# Base_Board.net
KiCad netlist of a schematic drawn in EAGLE
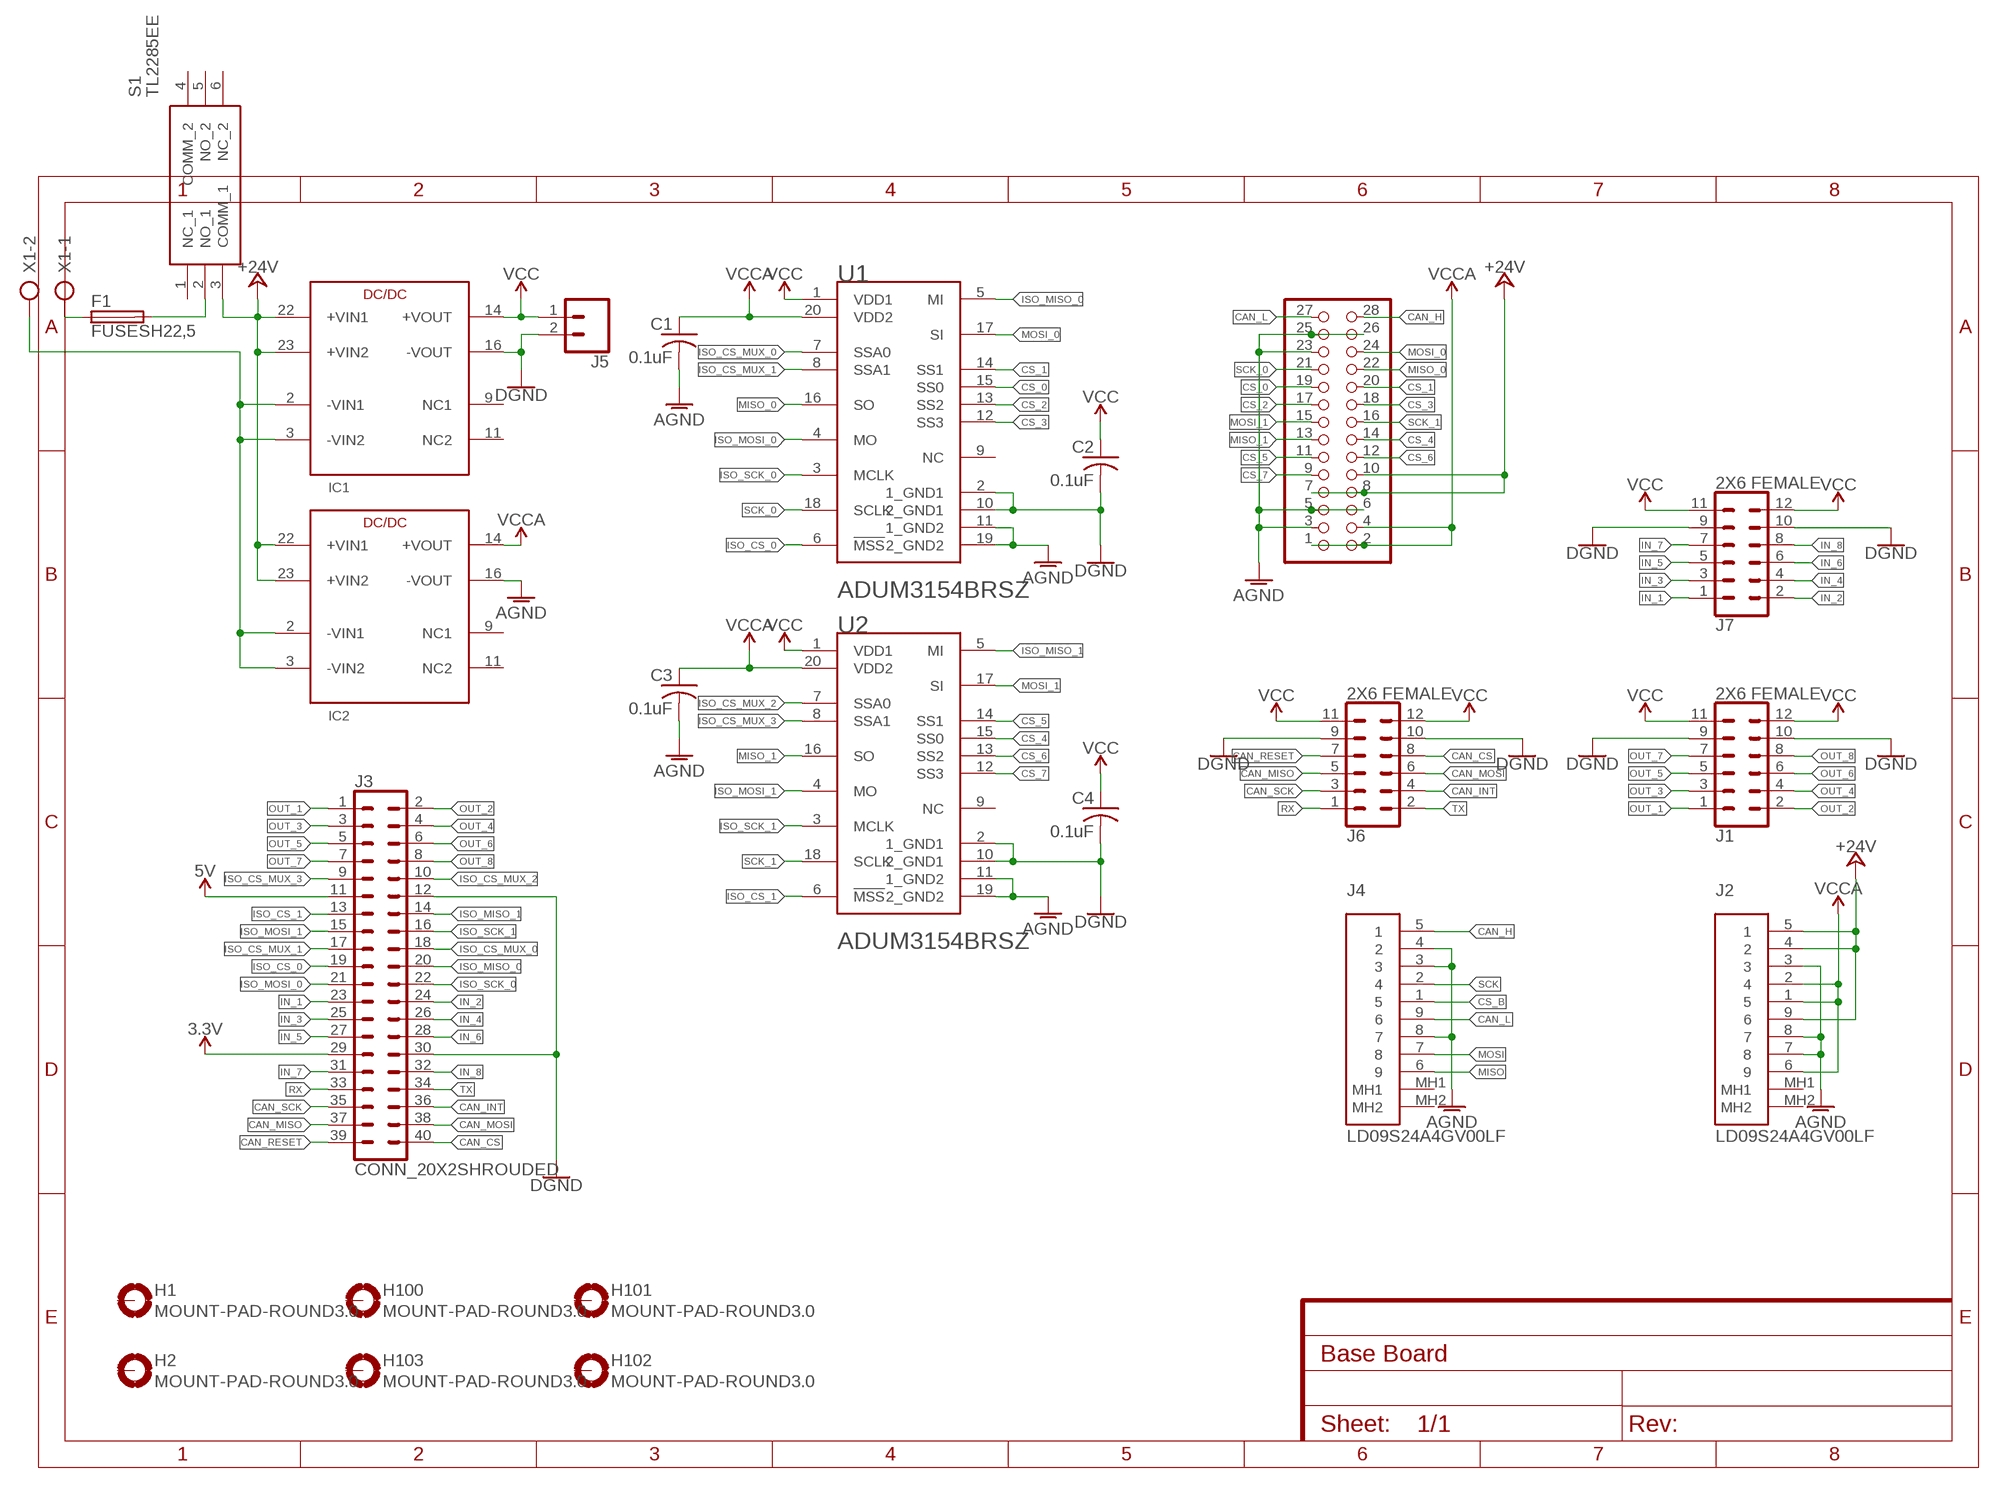
[diagram p0: schematic, sheet 1]

(export (version "E")
  (design (tool "Eeschema 10.0.6"))
  (components
    (comp (ref "C1")
      (value "0.1uF")
      (footprint "eagle-import:C0805")
      (libsource (lib "eagle-import") (part "C-USC0805"))
    )
    (comp (ref "C2")
      (value "0.1uF")
      (footprint "eagle-import:C0805")
      (libsource (lib "eagle-import") (part "C-USC0805"))
    )
    (comp (ref "C3")
      (value "0.1uF")
      (footprint "eagle-import:C0805")
      (libsource (lib "eagle-import") (part "C-USC0805"))
    )
    (comp (ref "C4")
      (value "0.1uF")
      (footprint "eagle-import:C0805")
      (libsource (lib "eagle-import") (part "C-USC0805"))
    )
    (comp (ref "F1")
      (value "FUSESH22,5")
      (footprint "eagle-import:SH22,5")
      (libsource (lib "eagle-import") (part "FUSESH22,5"))
    )
    (comp (ref "H1")
      (value "MOUNT-PAD-ROUND3.0")
      (footprint "eagle-import:3,0-PAD")
      (libsource (lib "eagle-import") (part "MOUNT-PAD-ROUND3.0"))
    )
    (comp (ref "H2")
      (value "MOUNT-PAD-ROUND3.0")
      (footprint "eagle-import:3,0-PAD")
      (libsource (lib "eagle-import") (part "MOUNT-PAD-ROUND3.0"))
    )
    (comp (ref "H100")
      (value "MOUNT-PAD-ROUND3.0")
      (footprint "eagle-import:3,0-PAD")
      (libsource (lib "eagle-import") (part "MOUNT-PAD-ROUND3.0"))
    )
    (comp (ref "H101")
      (value "MOUNT-PAD-ROUND3.0")
      (footprint "eagle-import:3,0-PAD")
      (libsource (lib "eagle-import") (part "MOUNT-PAD-ROUND3.0"))
    )
    (comp (ref "H102")
      (value "MOUNT-PAD-ROUND3.0")
      (footprint "eagle-import:3,0-PAD")
      (libsource (lib "eagle-import") (part "MOUNT-PAD-ROUND3.0"))
    )
    (comp (ref "H103")
      (value "MOUNT-PAD-ROUND3.0")
      (footprint "eagle-import:3,0-PAD")
      (libsource (lib "eagle-import") (part "MOUNT-PAD-ROUND3.0"))
    )
    (comp (ref "IC1")
      (value "TEL_5_SERIES")
      (footprint "eagle-import:TEL_5_SERIES")
      (libsource (lib "eagle-import") (part "TEL_5_SERIES"))
    )
    (comp (ref "IC2")
      (value "TEL_5_SERIES")
      (footprint "eagle-import:TEL_5_SERIES")
      (libsource (lib "eagle-import") (part "TEL_5_SERIES"))
    )
    (comp (ref "J1")
      (value "2X6 FEMALE")
      (footprint "eagle-import:2X6")
      (libsource (lib "eagle-import") (part "CONN_06X2PTH_FEMALE"))
    )
    (comp (ref "J2")
      (value "LD09S24A4GV00LF")
      (footprint "eagle-import:LD09S24A4GV00LF")
      (fields
        (field (name "DIGIKEY_PART_NUMBER") "609-5190-ND")
        (field (name "MANUFACTURER") "Amphenol ICC (FCI)")
        (field (name "CREATED_BY") "PCBLayout.com")
      )
      (libsource (lib "eagle-import") (part "LD09S24A4GV00LF"))
    )
    (comp (ref "J3")
      (value "CONN_20X2SHROUDED")
      (footprint "eagle-import:2X20_SHROUDED")
      (libsource (lib "eagle-import") (part "CONN_20X2SHROUDED"))
    )
    (comp (ref "J4")
      (value "LD09S24A4GV00LF")
      (footprint "eagle-import:LD09S24A4GV00LF")
      (fields
        (field (name "DIGIKEY_PART_NUMBER") "609-5190-ND")
        (field (name "MANUFACTURER") "Amphenol ICC (FCI)")
        (field (name "CREATED_BY") "PCBLayout.com")
      )
      (libsource (lib "eagle-import") (part "LD09S24A4GV00LF"))
    )
    (comp (ref "J5")
      (value "CONN_02POLAR_LOCK")
      (footprint "eagle-import:MOLEX-1X2_LOCK")
      (libsource (lib "eagle-import") (part "CONN_02POLAR_LOCK"))
    )
    (comp (ref "J6")
      (value "2X6 FEMALE")
      (footprint "eagle-import:2X6")
      (libsource (lib "eagle-import") (part "CONN_06X2PTH_FEMALE"))
    )
    (comp (ref "J7")
      (value "2X6 FEMALE")
      (footprint "eagle-import:2X6")
      (libsource (lib "eagle-import") (part "CONN_06X2PTH_FEMALE"))
    )
    (comp (ref "JP1")
      (value "PINHD-2X14/90")
      (footprint "eagle-import:2X14_90")
      (libsource (lib "eagle-import") (part "PINHD-2X14/90"))
    )
    (comp (ref "S1")
      (value "TL2285EE")
      (footprint "eagle-import:TL2285EE")
      (fields (field (name "MOUSER_PART_NUMBER") "612-TL2285EE"))
      (libsource (lib "eagle-import") (part "TL2285EE"))
    )
    (comp (ref "U1")
      (value "ANALOG_DEVICES_INC_ADUM3154BRSZANALOG_DEVICES_INC_ADUM3154BRSZ_0_0")
      (footprint "eagle-import:ANALOG_DEVICES_INC_ADUM3154BRSZ_0")
      (fields
        (field (name "DIGIKEY_PART_NUMBER") "ADUM3154BRSZ-ND")
        (field (name "MF") "Analog Devices Inc")
        (field (name "MOUSER_PART_NUMBER") "584-ADUM3154BRSZ")
      )
      (libsource (lib "eagle-import") (part "ANALOG_DEVICES_INC_ADUM3154BRSZANALOG_DEVICES_INC_ADUM3154BRSZ_0_0"))
    )
    (comp (ref "U2")
      (value "ANALOG_DEVICES_INC_ADUM3154BRSZANALOG_DEVICES_INC_ADUM3154BRSZ_0_0")
      (footprint "eagle-import:ANALOG_DEVICES_INC_ADUM3154BRSZ_0")
      (fields
        (field (name "DIGIKEY_PART_NUMBER") "ADUM3154BRSZ-ND")
        (field (name "MF") "Analog Devices Inc")
        (field (name "MOUSER_PART_NUMBER") "584-ADUM3154BRSZ")
      )
      (libsource (lib "eagle-import") (part "ANALOG_DEVICES_INC_ADUM3154BRSZANALOG_DEVICES_INC_ADUM3154BRSZ_0_0"))
    )
    (comp (ref "X1")
      (value "AK500/2-H")
      (footprint "eagle-import:AK500_2-H")
      (libsource (lib "eagle-import") (part "AK500/2-H"))
    )
  )
  (nets
    (net (code "1") (name "+24V") (class "Default")
      (node (ref "IC1") (pin "22") (pinfunction "+VIN1_22") (pintype "input"))
      (node (ref "IC1") (pin "23") (pinfunction "+VIN2_23") (pintype "input"))
      (node (ref "IC2") (pin "22") (pinfunction "+VIN1_22") (pintype "input"))
      (node (ref "IC2") (pin "23") (pinfunction "+VIN2_23") (pintype "input"))
      (node (ref "J2") (pin "4") (pinfunction "2_4") (pintype "passive"))
      (node (ref "J2") (pin "5") (pinfunction "1_5") (pintype "passive"))
      (node (ref "J2") (pin "9") (pinfunction "6_9") (pintype "passive"))
      (node (ref "JP1") (pin "10") (pinfunction "10_10") (pintype "passive"))
      (node (ref "JP1") (pin "7") (pinfunction "7_7") (pintype "passive"))
      (node (ref "JP1") (pin "8") (pinfunction "8_8") (pintype "passive"))
      (node (ref "S1") (pin "3") (pinfunction "COMM_1_3") (pintype "bidirectional"))
    )
    (net (code "2") (name "3.3V") (class "Default")
      (node (ref "J3") (pin "29") (pinfunction "29_29") (pintype "passive"))
    )
    (net (code "3") (name "5V") (class "Default")
      (node (ref "J3") (pin "11") (pinfunction "11_11") (pintype "passive"))
    )
    (net (code "4") (name "AGND") (class "Default")
      (node (ref "C1") (pin "2") (pinfunction "2_2") (pintype "passive"))
      (node (ref "C3") (pin "2") (pinfunction "2_2") (pintype "passive"))
      (node (ref "IC2") (pin "16") (pinfunction "-VOUT_16") (pintype "passive"))
      (node (ref "J2") (pin "3") (pinfunction "3_3") (pintype "passive"))
      (node (ref "J2") (pin "7") (pinfunction "8_7") (pintype "passive"))
      (node (ref "J2") (pin "8") (pinfunction "7_8") (pintype "passive"))
      (node (ref "J4") (pin "3") (pinfunction "3_3") (pintype "passive"))
      (node (ref "J4") (pin "4") (pinfunction "2_4") (pintype "passive"))
      (node (ref "J4") (pin "8") (pinfunction "7_8") (pintype "passive"))
      (node (ref "JP1") (pin "23") (pinfunction "23_23") (pintype "passive"))
      (node (ref "JP1") (pin "25") (pinfunction "25_25") (pintype "passive"))
      (node (ref "JP1") (pin "26") (pinfunction "26_26") (pintype "passive"))
      (node (ref "JP1") (pin "3") (pinfunction "3_3") (pintype "passive"))
      (node (ref "JP1") (pin "5") (pinfunction "5_5") (pintype "passive"))
      (node (ref "JP1") (pin "6") (pinfunction "6_6") (pintype "passive"))
      (node (ref "U1") (pin "11") (pinfunction "1_GND2_11") (pintype "power_in"))
      (node (ref "U1") (pin "19") (pinfunction "2_GND2_19") (pintype "power_in"))
      (node (ref "U2") (pin "11") (pinfunction "1_GND2_11") (pintype "power_in"))
      (node (ref "U2") (pin "19") (pinfunction "2_GND2_19") (pintype "power_in"))
    )
    (net (code "5") (name "CAN_CS") (class "Default")
      (node (ref "J3") (pin "40") (pinfunction "40_40") (pintype "passive"))
      (node (ref "J6") (pin "8") (pinfunction "8_8") (pintype "passive"))
    )
    (net (code "6") (name "CAN_H") (class "Default")
      (node (ref "J4") (pin "5") (pinfunction "1_5") (pintype "passive"))
      (node (ref "JP1") (pin "28") (pinfunction "28_28") (pintype "passive"))
    )
    (net (code "7") (name "CAN_INT") (class "Default")
      (node (ref "J3") (pin "36") (pinfunction "36_36") (pintype "passive"))
      (node (ref "J6") (pin "4") (pinfunction "4_4") (pintype "passive"))
    )
    (net (code "8") (name "CAN_L") (class "Default")
      (node (ref "J4") (pin "9") (pinfunction "6_9") (pintype "passive"))
      (node (ref "JP1") (pin "27") (pinfunction "27_27") (pintype "passive"))
    )
    (net (code "9") (name "CAN_MISO") (class "Default")
      (node (ref "J3") (pin "37") (pinfunction "37_37") (pintype "passive"))
      (node (ref "J6") (pin "5") (pinfunction "5_5") (pintype "passive"))
    )
    (net (code "10") (name "CAN_MOSI") (class "Default")
      (node (ref "J3") (pin "38") (pinfunction "38_38") (pintype "passive"))
      (node (ref "J6") (pin "6") (pinfunction "6_6") (pintype "passive"))
    )
    (net (code "11") (name "CAN_RESET") (class "Default")
      (node (ref "J3") (pin "39") (pinfunction "39_39") (pintype "passive"))
      (node (ref "J6") (pin "7") (pinfunction "7_7") (pintype "passive"))
    )
    (net (code "12") (name "CAN_SCK") (class "Default")
      (node (ref "J3") (pin "35") (pinfunction "35_35") (pintype "passive"))
      (node (ref "J6") (pin "3") (pinfunction "3_3") (pintype "passive"))
    )
    (net (code "13") (name "CS_0") (class "Default")
      (node (ref "JP1") (pin "19") (pinfunction "19_19") (pintype "passive"))
      (node (ref "U1") (pin "15") (pinfunction "SS0_15") (pintype "output"))
    )
    (net (code "14") (name "CS_1") (class "Default")
      (node (ref "JP1") (pin "20") (pinfunction "20_20") (pintype "passive"))
      (node (ref "U1") (pin "14") (pinfunction "SS1_14") (pintype "output"))
    )
    (net (code "15") (name "CS_2") (class "Default")
      (node (ref "JP1") (pin "17") (pinfunction "17_17") (pintype "passive"))
      (node (ref "U1") (pin "13") (pinfunction "SS2_13") (pintype "output"))
    )
    (net (code "16") (name "CS_3") (class "Default")
      (node (ref "JP1") (pin "18") (pinfunction "18_18") (pintype "passive"))
      (node (ref "U1") (pin "12") (pinfunction "SS3_12") (pintype "output"))
    )
    (net (code "17") (name "CS_4") (class "Default")
      (node (ref "JP1") (pin "14") (pinfunction "14_14") (pintype "passive"))
      (node (ref "U2") (pin "15") (pinfunction "SS0_15") (pintype "output"))
    )
    (net (code "18") (name "CS_5") (class "Default")
      (node (ref "JP1") (pin "11") (pinfunction "11_11") (pintype "passive"))
      (node (ref "U2") (pin "14") (pinfunction "SS1_14") (pintype "output"))
    )
    (net (code "19") (name "CS_6") (class "Default")
      (node (ref "JP1") (pin "12") (pinfunction "12_12") (pintype "passive"))
      (node (ref "U2") (pin "13") (pinfunction "SS2_13") (pintype "output"))
    )
    (net (code "20") (name "CS_7") (class "Default")
      (node (ref "JP1") (pin "9") (pinfunction "9_9") (pintype "passive"))
      (node (ref "U2") (pin "12") (pinfunction "SS3_12") (pintype "output"))
    )
    (net (code "21") (name "CS_B") (class "Default")
      (node (ref "J4") (pin "1") (pinfunction "5_1") (pintype "passive"))
    )
    (net (code "22") (name "DGND") (class "Default")
      (node (ref "C2") (pin "2") (pinfunction "2_2") (pintype "passive"))
      (node (ref "C4") (pin "2") (pinfunction "2_2") (pintype "passive"))
      (node (ref "IC1") (pin "16") (pinfunction "-VOUT_16") (pintype "passive"))
      (node (ref "J1") (pin "10") (pinfunction "10_10") (pintype "passive"))
      (node (ref "J1") (pin "9") (pinfunction "9_9") (pintype "passive"))
      (node (ref "J3") (pin "12") (pinfunction "12_12") (pintype "passive"))
      (node (ref "J3") (pin "30") (pinfunction "30_30") (pintype "passive"))
      (node (ref "J5") (pin "2") (pinfunction "2_2") (pintype "passive"))
      (node (ref "J6") (pin "10") (pinfunction "10_10") (pintype "passive"))
      (node (ref "J6") (pin "9") (pinfunction "9_9") (pintype "passive"))
      (node (ref "J7") (pin "10") (pinfunction "10_10") (pintype "passive"))
      (node (ref "J7") (pin "9") (pinfunction "9_9") (pintype "passive"))
      (node (ref "U1") (pin "10") (pinfunction "2_GND1_10") (pintype "power_in"))
      (node (ref "U1") (pin "2") (pinfunction "1_GND1_2") (pintype "power_in"))
      (node (ref "U2") (pin "10") (pinfunction "2_GND1_10") (pintype "power_in"))
      (node (ref "U2") (pin "2") (pinfunction "1_GND1_2") (pintype "power_in"))
    )
    (net (code "23") (name "IN_1") (class "Default")
      (node (ref "J3") (pin "23") (pinfunction "23_23") (pintype "passive"))
      (node (ref "J7") (pin "1") (pinfunction "1_1") (pintype "passive"))
    )
    (net (code "24") (name "IN_2") (class "Default")
      (node (ref "J3") (pin "24") (pinfunction "24_24") (pintype "passive"))
      (node (ref "J7") (pin "2") (pinfunction "2_2") (pintype "passive"))
    )
    (net (code "25") (name "IN_3") (class "Default")
      (node (ref "J3") (pin "25") (pinfunction "25_25") (pintype "passive"))
      (node (ref "J7") (pin "3") (pinfunction "3_3") (pintype "passive"))
    )
    (net (code "26") (name "IN_4") (class "Default")
      (node (ref "J3") (pin "26") (pinfunction "26_26") (pintype "passive"))
      (node (ref "J7") (pin "4") (pinfunction "4_4") (pintype "passive"))
    )
    (net (code "27") (name "IN_5") (class "Default")
      (node (ref "J3") (pin "27") (pinfunction "27_27") (pintype "passive"))
      (node (ref "J7") (pin "5") (pinfunction "5_5") (pintype "passive"))
    )
    (net (code "28") (name "IN_6") (class "Default")
      (node (ref "J3") (pin "28") (pinfunction "28_28") (pintype "passive"))
      (node (ref "J7") (pin "6") (pinfunction "6_6") (pintype "passive"))
    )
    (net (code "29") (name "IN_7") (class "Default")
      (node (ref "J3") (pin "31") (pinfunction "31_31") (pintype "passive"))
      (node (ref "J7") (pin "7") (pinfunction "7_7") (pintype "passive"))
    )
    (net (code "30") (name "IN_8") (class "Default")
      (node (ref "J3") (pin "32") (pinfunction "32_32") (pintype "passive"))
      (node (ref "J7") (pin "8") (pinfunction "8_8") (pintype "passive"))
    )
    (net (code "31") (name "ISO_CS_0") (class "Default")
      (node (ref "J3") (pin "19") (pinfunction "19_19") (pintype "passive"))
      (node (ref "U1") (pin "6") (pinfunction "~{MSS}_6") (pintype "input"))
    )
    (net (code "32") (name "ISO_CS_1") (class "Default")
      (node (ref "J3") (pin "13") (pinfunction "13_13") (pintype "passive"))
      (node (ref "U2") (pin "6") (pinfunction "~{MSS}_6") (pintype "input"))
    )
    (net (code "33") (name "ISO_CS_MUX_0") (class "Default")
      (node (ref "J3") (pin "18") (pinfunction "18_18") (pintype "passive"))
      (node (ref "U1") (pin "7") (pinfunction "SSA0_7") (pintype "input"))
    )
    (net (code "34") (name "ISO_CS_MUX_1") (class "Default")
      (node (ref "J3") (pin "17") (pinfunction "17_17") (pintype "passive"))
      (node (ref "U1") (pin "8") (pinfunction "SSA1_8") (pintype "input"))
    )
    (net (code "35") (name "ISO_CS_MUX_2") (class "Default")
      (node (ref "J3") (pin "10") (pinfunction "10_10") (pintype "passive"))
      (node (ref "U2") (pin "7") (pinfunction "SSA0_7") (pintype "input"))
    )
    (net (code "36") (name "ISO_CS_MUX_3") (class "Default")
      (node (ref "J3") (pin "9") (pinfunction "9_9") (pintype "passive"))
      (node (ref "U2") (pin "8") (pinfunction "SSA1_8") (pintype "input"))
    )
    (net (code "37") (name "ISO_MISO_0") (class "Default")
      (node (ref "J3") (pin "20") (pinfunction "20_20") (pintype "passive"))
      (node (ref "U1") (pin "5") (pinfunction "MI_5") (pintype "output"))
    )
    (net (code "38") (name "ISO_MISO_1") (class "Default")
      (node (ref "J3") (pin "14") (pinfunction "14_14") (pintype "passive"))
      (node (ref "U2") (pin "5") (pinfunction "MI_5") (pintype "output"))
    )
    (net (code "39") (name "ISO_MOSI_0") (class "Default")
      (node (ref "J3") (pin "21") (pinfunction "21_21") (pintype "passive"))
      (node (ref "U1") (pin "4") (pinfunction "MO_4") (pintype "input"))
    )
    (net (code "40") (name "ISO_MOSI_1") (class "Default")
      (node (ref "J3") (pin "15") (pinfunction "15_15") (pintype "passive"))
      (node (ref "U2") (pin "4") (pinfunction "MO_4") (pintype "input"))
    )
    (net (code "41") (name "ISO_SCK_0") (class "Default")
      (node (ref "J3") (pin "22") (pinfunction "22_22") (pintype "passive"))
      (node (ref "U1") (pin "3") (pinfunction "MCLK_3") (pintype "input"))
    )
    (net (code "42") (name "ISO_SCK_1") (class "Default")
      (node (ref "J3") (pin "16") (pinfunction "16_16") (pintype "passive"))
      (node (ref "U2") (pin "3") (pinfunction "MCLK_3") (pintype "input"))
    )
    (net (code "43") (name "MISO") (class "Default")
      (node (ref "J4") (pin "6") (pinfunction "9_6") (pintype "passive"))
    )
    (net (code "44") (name "MISO_0") (class "Default")
      (node (ref "JP1") (pin "22") (pinfunction "22_22") (pintype "passive"))
      (node (ref "U1") (pin "16") (pinfunction "SO_16") (pintype "input"))
    )
    (net (code "45") (name "MISO_1") (class "Default")
      (node (ref "JP1") (pin "13") (pinfunction "13_13") (pintype "passive"))
      (node (ref "U2") (pin "16") (pinfunction "SO_16") (pintype "input"))
    )
    (net (code "46") (name "MOSI") (class "Default")
      (node (ref "J4") (pin "7") (pinfunction "8_7") (pintype "passive"))
    )
    (net (code "47") (name "MOSI_0") (class "Default")
      (node (ref "JP1") (pin "24") (pinfunction "24_24") (pintype "passive"))
      (node (ref "U1") (pin "17") (pinfunction "SI_17") (pintype "output"))
    )
    (net (code "48") (name "MOSI_1") (class "Default")
      (node (ref "JP1") (pin "15") (pinfunction "15_15") (pintype "passive"))
      (node (ref "U2") (pin "17") (pinfunction "SI_17") (pintype "output"))
    )
    (net (code "49") (name "Net-(IC1--VIN1)") (class "Default")
      (node (ref "IC1") (pin "2") (pinfunction "-VIN1_2") (pintype "input"))
      (node (ref "IC1") (pin "3") (pinfunction "-VIN2_3") (pintype "input"))
      (node (ref "IC2") (pin "2") (pinfunction "-VIN1_2") (pintype "input"))
      (node (ref "IC2") (pin "3") (pinfunction "-VIN2_3") (pintype "input"))
      (node (ref "X1") (pin "2") (pinfunction "KL_2") (pintype "passive"))
    )
    (net (code "50") (name "Net-(S1-NO_1)") (class "Default")
      (node (ref "F1") (pin "2") (pinfunction "2_2") (pintype "passive"))
      (node (ref "S1") (pin "2") (pinfunction "NO_1_2") (pintype "bidirectional"))
    )
    (net (code "51") (name "Net-(X1A-KL)") (class "Default")
      (node (ref "F1") (pin "1") (pinfunction "1_1") (pintype "passive"))
      (node (ref "X1") (pin "1") (pinfunction "KL_1") (pintype "passive"))
    )
    (net (code "52") (name "OUT_1") (class "Default")
      (node (ref "J1") (pin "1") (pinfunction "1_1") (pintype "passive"))
      (node (ref "J3") (pin "1") (pinfunction "1_1") (pintype "passive"))
    )
    (net (code "53") (name "OUT_2") (class "Default")
      (node (ref "J1") (pin "2") (pinfunction "2_2") (pintype "passive"))
      (node (ref "J3") (pin "2") (pinfunction "2_2") (pintype "passive"))
    )
    (net (code "54") (name "OUT_3") (class "Default")
      (node (ref "J1") (pin "3") (pinfunction "3_3") (pintype "passive"))
      (node (ref "J3") (pin "3") (pinfunction "3_3") (pintype "passive"))
    )
    (net (code "55") (name "OUT_4") (class "Default")
      (node (ref "J1") (pin "4") (pinfunction "4_4") (pintype "passive"))
      (node (ref "J3") (pin "4") (pinfunction "4_4") (pintype "passive"))
    )
    (net (code "56") (name "OUT_5") (class "Default")
      (node (ref "J1") (pin "5") (pinfunction "5_5") (pintype "passive"))
      (node (ref "J3") (pin "5") (pinfunction "5_5") (pintype "passive"))
    )
    (net (code "57") (name "OUT_6") (class "Default")
      (node (ref "J1") (pin "6") (pinfunction "6_6") (pintype "passive"))
      (node (ref "J3") (pin "6") (pinfunction "6_6") (pintype "passive"))
    )
    (net (code "58") (name "OUT_7") (class "Default")
      (node (ref "J1") (pin "7") (pinfunction "7_7") (pintype "passive"))
      (node (ref "J3") (pin "7") (pinfunction "7_7") (pintype "passive"))
    )
    (net (code "59") (name "OUT_8") (class "Default")
      (node (ref "J1") (pin "8") (pinfunction "8_8") (pintype "passive"))
      (node (ref "J3") (pin "8") (pinfunction "8_8") (pintype "passive"))
    )
    (net (code "60") (name "RX") (class "Default")
      (node (ref "J3") (pin "33") (pinfunction "33_33") (pintype "passive"))
      (node (ref "J6") (pin "1") (pinfunction "1_1") (pintype "passive"))
    )
    (net (code "61") (name "SCK") (class "Default")
      (node (ref "J4") (pin "2") (pinfunction "4_2") (pintype "passive"))
    )
    (net (code "62") (name "SCK_0") (class "Default")
      (node (ref "JP1") (pin "21") (pinfunction "21_21") (pintype "passive"))
      (node (ref "U1") (pin "18") (pinfunction "SCLK_18") (pintype "input"))
    )
    (net (code "63") (name "SCK_1") (class "Default")
      (node (ref "JP1") (pin "16") (pinfunction "16_16") (pintype "passive"))
      (node (ref "U2") (pin "18") (pinfunction "SCLK_18") (pintype "input"))
    )
    (net (code "64") (name "TX") (class "Default")
      (node (ref "J3") (pin "34") (pinfunction "34_34") (pintype "passive"))
      (node (ref "J6") (pin "2") (pinfunction "2_2") (pintype "passive"))
    )
    (net (code "65") (name "VCC") (class "Default")
      (node (ref "C2") (pin "1") (pinfunction "1_1") (pintype "passive"))
      (node (ref "C4") (pin "1") (pinfunction "1_1") (pintype "passive"))
      (node (ref "IC1") (pin "14") (pinfunction "+VOUT_14") (pintype "passive"))
      (node (ref "J1") (pin "11") (pinfunction "11_11") (pintype "passive"))
      (node (ref "J1") (pin "12") (pinfunction "12_12") (pintype "passive"))
      (node (ref "J5") (pin "1") (pinfunction "1_1") (pintype "passive"))
      (node (ref "J6") (pin "11") (pinfunction "11_11") (pintype "passive"))
      (node (ref "J6") (pin "12") (pinfunction "12_12") (pintype "passive"))
      (node (ref "J7") (pin "11") (pinfunction "11_11") (pintype "passive"))
      (node (ref "J7") (pin "12") (pinfunction "12_12") (pintype "passive"))
      (node (ref "U1") (pin "1") (pinfunction "VDD1_1") (pintype "power_in"))
      (node (ref "U2") (pin "1") (pinfunction "VDD1_1") (pintype "power_in"))
    )
    (net (code "66") (name "VCCA") (class "Default")
      (node (ref "C1") (pin "1") (pinfunction "1_1") (pintype "passive"))
      (node (ref "C3") (pin "1") (pinfunction "1_1") (pintype "passive"))
      (node (ref "IC2") (pin "14") (pinfunction "+VOUT_14") (pintype "passive"))
      (node (ref "J2") (pin "1") (pinfunction "5_1") (pintype "passive"))
      (node (ref "J2") (pin "2") (pinfunction "4_2") (pintype "passive"))
      (node (ref "J2") (pin "6") (pinfunction "9_6") (pintype "passive"))
      (node (ref "JP1") (pin "1") (pinfunction "1_1") (pintype "passive"))
      (node (ref "JP1") (pin "2") (pinfunction "2_2") (pintype "passive"))
      (node (ref "JP1") (pin "4") (pinfunction "4_4") (pintype "passive"))
      (node (ref "U1") (pin "20") (pinfunction "VDD2_20") (pintype "power_in"))
      (node (ref "U2") (pin "20") (pinfunction "VDD2_20") (pintype "power_in"))
    )
    (net (code "67") (name "unconnected-(H1-MOUNT-PadB3,0)") (class "Default")
      (node (ref "H1") (pin "B3,0") (pinfunction "MOUNT_B3,0") (pintype "passive"))
    )
    (net (code "68") (name "unconnected-(H2-MOUNT-PadB3,0)") (class "Default")
      (node (ref "H2") (pin "B3,0") (pinfunction "MOUNT_B3,0") (pintype "passive"))
    )
    (net (code "69") (name "unconnected-(H100-MOUNT-PadB3,0)") (class "Default")
      (node (ref "H100") (pin "B3,0") (pinfunction "MOUNT_B3,0") (pintype "passive"))
    )
    (net (code "70") (name "unconnected-(H101-MOUNT-PadB3,0)") (class "Default")
      (node (ref "H101") (pin "B3,0") (pinfunction "MOUNT_B3,0") (pintype "passive"))
    )
    (net (code "71") (name "unconnected-(H102-MOUNT-PadB3,0)") (class "Default")
      (node (ref "H102") (pin "B3,0") (pinfunction "MOUNT_B3,0") (pintype "passive"))
    )
    (net (code "72") (name "unconnected-(H103-MOUNT-PadB3,0)") (class "Default")
      (node (ref "H103") (pin "B3,0") (pinfunction "MOUNT_B3,0") (pintype "passive"))
    )
    (net (code "73") (name "unconnected-(IC1-NC1-Pad9)") (class "Default")
      (node (ref "IC1") (pin "9") (pinfunction "NC1_9") (pintype "no_connect"))
    )
    (net (code "74") (name "unconnected-(IC1-NC2-Pad11)") (class "Default")
      (node (ref "IC1") (pin "11") (pinfunction "NC2_11") (pintype "no_connect"))
    )
    (net (code "75") (name "unconnected-(IC2-NC1-Pad9)") (class "Default")
      (node (ref "IC2") (pin "9") (pinfunction "NC1_9") (pintype "no_connect"))
    )
    (net (code "76") (name "unconnected-(IC2-NC2-Pad11)") (class "Default")
      (node (ref "IC2") (pin "11") (pinfunction "NC2_11") (pintype "no_connect"))
    )
    (net (code "77") (name "unconnected-(J2-PadMH1)") (class "Default")
      (node (ref "J2") (pin "MH1") (pinfunction "MH1_MH1") (pintype "passive"))
    )
    (net (code "78") (name "unconnected-(J2-PadMH2)") (class "Default")
      (node (ref "J2") (pin "MH2") (pinfunction "MH2_MH2") (pintype "passive"))
    )
    (net (code "79") (name "unconnected-(J4-PadMH1)") (class "Default")
      (node (ref "J4") (pin "MH1") (pinfunction "MH1_MH1") (pintype "passive"))
    )
    (net (code "80") (name "unconnected-(J4-PadMH2)") (class "Default")
      (node (ref "J4") (pin "MH2") (pinfunction "MH2_MH2") (pintype "passive"))
    )
    (net (code "81") (name "unconnected-(S1-COMM_2-Pad4)") (class "Default")
      (node (ref "S1") (pin "4") (pinfunction "COMM_2_4") (pintype "bidirectional"))
    )
    (net (code "82") (name "unconnected-(S1-NC_1-Pad1)") (class "Default")
      (node (ref "S1") (pin "1") (pinfunction "NC_1_1") (pintype "bidirectional"))
    )
    (net (code "83") (name "unconnected-(S1-NC_2-Pad6)") (class "Default")
      (node (ref "S1") (pin "6") (pinfunction "NC_2_6") (pintype "bidirectional"))
    )
    (net (code "84") (name "unconnected-(S1-NO_2-Pad5)") (class "Default")
      (node (ref "S1") (pin "5") (pinfunction "NO_2_5") (pintype "bidirectional"))
    )
    (net (code "85") (name "unconnected-(U1-NC-Pad9)") (class "Default")
      (node (ref "U1") (pin "9") (pinfunction "NC_9") (pintype "passive"))
    )
    (net (code "86") (name "unconnected-(U2-NC-Pad9)") (class "Default")
      (node (ref "U2") (pin "9") (pinfunction "NC_9") (pintype "passive"))
    )
  )
)
